# driver_V1_1.net
KiCad netlist of a schematic drawn in Altium Designer
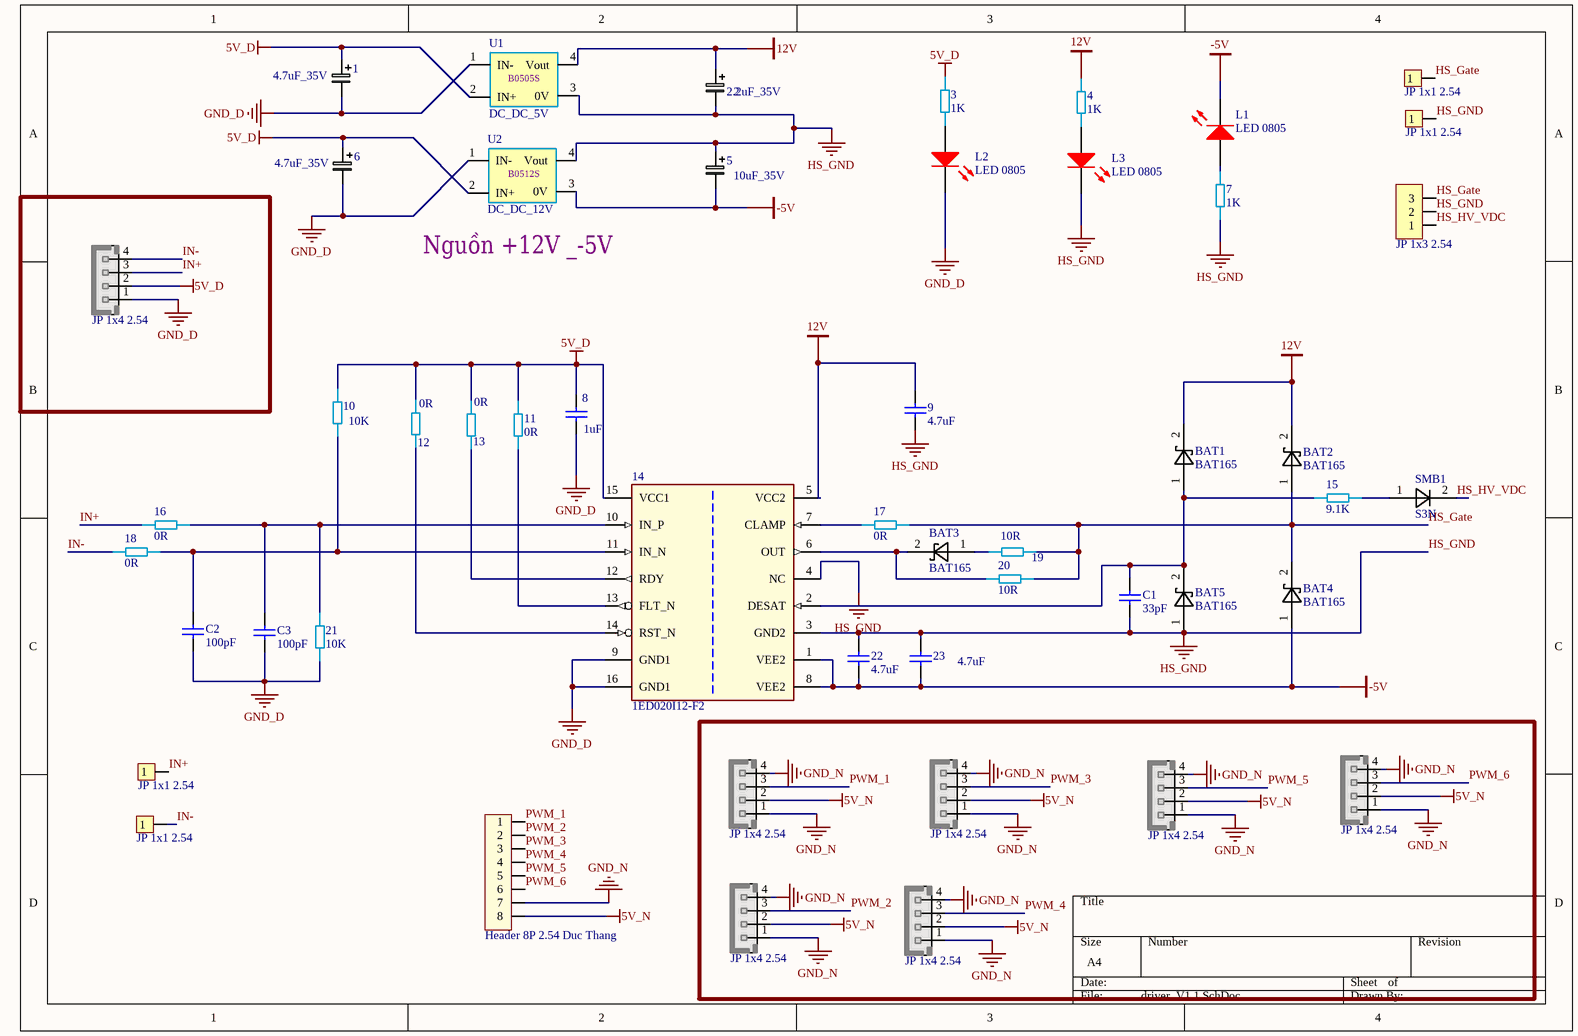
[diagram p0: driver_V1.1.SchDoc]

(export (version "E")
  (design (tool "Eeschema 10.0.6"))
  (components
    (comp (ref "1")
      (value "4.7uF_35V")
      (footprint "tu_4x5.4mm")
      (description "capacitor_electric")
      (libsource (lib "labari_altium1") (part "capacitor_electric"))
    )
    (comp (ref "2")
      (value "2.2uF_35V")
      (footprint "tu_4x5.4mm")
      (description "capacitor_electric")
      (libsource (lib "labari_altium1") (part "capacitor_electric"))
    )
    (comp (ref "3")
      (value "1K")
      (footprint "RES1206")
      (libsource (lib "labari_altium1") (part "311-0.0GRTR-ND"))
    )
    (comp (ref "4")
      (value "1K")
      (footprint "RES1206")
      (libsource (lib "labari_altium1") (part "311-0.0GRTR-ND"))
    )
    (comp (ref "5")
      (value "10uF_35V")
      (footprint "tu_4x5.4mm")
      (description "capacitor_electric")
      (libsource (lib "labari_altium1") (part "capacitor_electric"))
    )
    (comp (ref "6")
      (value "4.7uF_35V")
      (footprint "tu_4x5.4mm")
      (description "capacitor_electric")
      (libsource (lib "labari_altium1") (part "capacitor_electric"))
    )
    (comp (ref "7")
      (value "1K")
      (footprint "RES1206")
      (libsource (lib "labari_altium1") (part "311-0.0GRTR-ND"))
    )
    (comp (ref "8")
      (value "1uF")
      (footprint "Tu 0805_N")
      (libsource (lib "labari_altium1") (part "cap_0805"))
    )
    (comp (ref "9")
      (value "4.7uF")
      (footprint "tu 1206_N")
      (libsource (lib "labari_altium1") (part "cap_1210"))
    )
    (comp (ref "10")
      (value "10K")
      (footprint "RES1206")
      (libsource (lib "labari_altium1") (part "311-0.0GRTR-ND"))
    )
    (comp (ref "11")
      (value "0R")
      (footprint "RES1206")
      (libsource (lib "labari_altium1") (part "311-0.0GRTR-ND"))
    )
    (comp (ref "12")
      (value "0R")
      (footprint "RES1206")
      (libsource (lib "labari_altium1") (part "311-0.0GRTR-ND"))
    )
    (comp (ref "13")
      (value "0R")
      (footprint "RES1206")
      (libsource (lib "labari_altium1") (part "311-0.0GRTR-ND"))
    )
    (comp (ref "14")
      (value "1ED020I12-F2")
      (footprint "SOIC127P1028X264-16N-1")
      (description "Single IGBT Driver IC")
      (fields (field (name "MANUFACTURER") "Infineon Technologies"))
      (libsource (lib "labari_altium1") (part "1ED020I12-F2"))
    )
    (comp (ref "15")
      (value "9.1K")
      (footprint "RES_2512")
      (libsource (lib "labari_altium1") (part "311-0.0GRTR-ND"))
    )
    (comp (ref "16")
      (value "0R")
      (footprint "RES1206")
      (libsource (lib "labari_altium1") (part "311-0.0GRTR-ND"))
    )
    (comp (ref "17")
      (value "0R")
      (footprint "RES_2512")
      (libsource (lib "labari_altium1") (part "311-0.0GRTR-ND"))
    )
    (comp (ref "18")
      (value "0R")
      (footprint "RES1206")
      (libsource (lib "labari_altium1") (part "311-0.0GRTR-ND"))
    )
    (comp (ref "19")
      (value "10R")
      (footprint "RES_2512")
      (libsource (lib "labari_altium1") (part "311-0.0GRTR-ND"))
    )
    (comp (ref "20")
      (value "10R")
      (footprint "RES_2512")
      (libsource (lib "labari_altium1") (part "311-0.0GRTR-ND"))
    )
    (comp (ref "21")
      (value "10K")
      (footprint "RES1206")
      (libsource (lib "labari_altium1") (part "311-0.0GRTR-ND"))
    )
    (comp (ref "22")
      (value "4.7uF")
      (footprint "tu 1206_N")
      (libsource (lib "labari_altium1") (part "cap_1210"))
    )
    (comp (ref "23")
      (value "4.7uF")
      (footprint "tu 1206_N")
      (libsource (lib "labari_altium1") (part "cap_1210"))
    )
    (comp (ref "BAT1") (value "BAT165") (footprint "SMB") (libsource (lib "labari_altium1") (part "BAT165")))
    (comp (ref "BAT2") (value "BAT165") (footprint "SMB") (libsource (lib "labari_altium1") (part "BAT165")))
    (comp (ref "BAT3") (value "BAT165") (footprint "SMB") (libsource (lib "labari_altium1") (part "BAT165")))
    (comp (ref "BAT4") (value "BAT165") (footprint "SMB") (libsource (lib "labari_altium1") (part "BAT165")))
    (comp (ref "BAT5") (value "BAT165") (footprint "SMB") (libsource (lib "labari_altium1") (part "BAT165")))
    (comp (ref "C1")
      (value "33pF")
      (footprint "Tu 0805_N")
      (libsource (lib "labari_altium1") (part "cap_0805"))
    )
    (comp (ref "C2")
      (value "100pF")
      (footprint "Tu 0805_N")
      (libsource (lib "labari_altium1") (part "cap_0805"))
    )
    (comp (ref "C3")
      (value "100pF")
      (footprint "Tu 0805_N")
      (libsource (lib "labari_altium1") (part "cap_0805"))
    )
    (comp (ref "H1")
      (value "Header 8P 2.54 Duc Thang")
      (footprint "XH2.54M-8")
      (description "Cắm")
      (libsource (lib "labari_altium1") (part "Header 8P 2.54 Duc Thang"))
    )
    (comp (ref "JP1")
      (value "JP 1x1 2.54")
      (footprint "test_point")
      (description "Cắm")
      (libsource (lib "labari_altium1") (part "JP 1x1 2.54 Duc Thang"))
    )
    (comp (ref "JP2")
      (value "JP 1x1 2.54")
      (footprint "test_point")
      (description "Cắm")
      (libsource (lib "labari_altium1") (part "JP 1x1 2.54 Duc Thang"))
    )
    (comp (ref "JP3")
      (value "JP 1x3 2.54")
      (footprint "XH2.54M-3")
      (description "Cắm")
      (libsource (lib "labari_altium1") (part "JP 1x3 2.54 Duc Cong"))
    )
    (comp (ref "JP4")
      (value "JP 1x4 2.54")
      (footprint "XH2.54M-4")
      (description "Cắm")
      (libsource (lib "labari_altium1") (part "JP 1x4 2.54 Duc Thang"))
    )
    (comp (ref "JP5")
      (value "JP 1x1 2.54")
      (footprint "test_point")
      (description "Cắm")
      (libsource (lib "labari_altium1") (part "JP 1x1 2.54 Duc Thang"))
    )
    (comp (ref "JP6")
      (value "JP 1x1 2.54")
      (footprint "test_point")
      (description "Cắm")
      (libsource (lib "labari_altium1") (part "JP 1x1 2.54 Duc Thang"))
    )
    (comp (ref "JP7")
      (value "JP 1x4 2.54")
      (footprint "XH2.54M-4")
      (description "Cắm")
      (libsource (lib "labari_altium1") (part "JP 1x4 2.54 Duc Thang"))
    )
    (comp (ref "JP8")
      (value "JP 1x4 2.54")
      (footprint "XH2.54M-4")
      (description "Cắm")
      (libsource (lib "labari_altium1") (part "JP 1x4 2.54 Duc Thang"))
    )
    (comp (ref "JP9")
      (value "JP 1x4 2.54")
      (footprint "XH2.54M-4")
      (description "Cắm")
      (libsource (lib "labari_altium1") (part "JP 1x4 2.54 Duc Thang"))
    )
    (comp (ref "JP10")
      (value "JP 1x4 2.54")
      (footprint "XH2.54M-4")
      (description "Cắm")
      (libsource (lib "labari_altium1") (part "JP 1x4 2.54 Duc Thang"))
    )
    (comp (ref "JP11")
      (value "JP 1x4 2.54")
      (footprint "XH2.54M-4")
      (description "Cắm")
      (libsource (lib "labari_altium1") (part "JP 1x4 2.54 Duc Thang"))
    )
    (comp (ref "JP12")
      (value "JP 1x4 2.54")
      (footprint "XH2.54M-4")
      (description "Cắm")
      (libsource (lib "labari_altium1") (part "JP 1x4 2.54 Duc Thang"))
    )
    (comp (ref "L1")
      (value "LED 0805")
      (footprint "LED-0805-Red")
      (description "Dán")
      (libsource (lib "labari_altium1") (part "LED 0805 Do"))
    )
    (comp (ref "L2")
      (value "LED 0805")
      (footprint "LED-0805-Red")
      (description "Dán")
      (libsource (lib "labari_altium1") (part "LED 0805 Do"))
    )
    (comp (ref "L3")
      (value "LED 0805")
      (footprint "LED-0805-Red")
      (description "Dán")
      (libsource (lib "labari_altium1") (part "LED 0805 Do"))
    )
    (comp (ref "SMB1") (value "S3N") (footprint "SMB") (libsource (lib "labari_altium1") (part "S3A-S3N")))
    (comp (ref "U1")
      (value "DC_DC_5V")
      (footprint "B0505S/D-1W")
      (libsource (lib "labari_altium1") (part "DC_DC_5v"))
    )
    (comp (ref "U2")
      (value "DC_DC_12V")
      (footprint "B0512S/D-1W")
      (libsource (lib "labari_altium1") (part "DC_DC_12v"))
    )
  )
  (nets
    (net (code "1") (name "-5V") (class "Default")
      (node (ref "14") (pin "1") (pinfunction "VEE2_1") (pintype "power_in"))
      (node (ref "14") (pin "8") (pinfunction "VEE2_8") (pintype "power_in"))
      (node (ref "22") (pin "1") (pinfunction "1_1") (pintype "passive"))
      (node (ref "23") (pin "1") (pinfunction "1_1") (pintype "passive"))
      (node (ref "5") (pin "2") (pinfunction "2_2") (pintype "passive"))
      (node (ref "BAT4") (pin "1") (pinfunction "1_1") (pintype "passive"))
      (node (ref "L1") (pin "2") (pinfunction "K_2") (pintype "passive"))
      (node (ref "U2") (pin "3") (pinfunction "0V_3") (pintype "passive"))
    )
    (net (code "2") (name "/HS_Gate") (class "Default")
      (node (ref "17") (pin "2") (pinfunction "2_2") (pintype "passive"))
      (node (ref "19") (pin "2") (pinfunction "2_2") (pintype "passive"))
      (node (ref "20") (pin "2") (pinfunction "2_2") (pintype "passive"))
      (node (ref "BAT2") (pin "1") (pinfunction "1_1") (pintype "passive"))
      (node (ref "BAT4") (pin "2") (pinfunction "2_2") (pintype "passive"))
      (node (ref "JP1") (pin "1") (pinfunction "1_1") (pintype "passive"))
      (node (ref "JP3") (pin "3") (pinfunction "3_3") (pintype "passive"))
    )
    (net (code "3") (name "/HS_HV_VDC") (class "Default")
      (node (ref "JP3") (pin "1") (pinfunction "1_1") (pintype "passive"))
      (node (ref "SMB1") (pin "2") (pinfunction "2_2") (pintype "passive"))
    )
    (net (code "4") (name "/IN+") (class "Default")
      (node (ref "16") (pin "2") (pinfunction "2_2") (pintype "passive"))
      (node (ref "JP4") (pin "3") (pinfunction "3_3") (pintype "passive"))
      (node (ref "JP5") (pin "1") (pinfunction "1_1") (pintype "passive"))
    )
    (net (code "5") (name "/IN-") (class "Default")
      (node (ref "18") (pin "2") (pinfunction "2_2") (pintype "passive"))
      (node (ref "JP4") (pin "4") (pinfunction "4_4") (pintype "passive"))
      (node (ref "JP6") (pin "1") (pinfunction "1_1") (pintype "passive"))
    )
    (net (code "6") (name "/PWM_1") (class "Default")
      (node (ref "H1") (pin "1") (pinfunction "1_1") (pintype "passive"))
      (node (ref "JP8") (pin "3") (pinfunction "3_3") (pintype "passive"))
    )
    (net (code "7") (name "/PWM_2") (class "Default")
      (node (ref "H1") (pin "2") (pinfunction "2_2") (pintype "passive"))
      (node (ref "JP11") (pin "3") (pinfunction "3_3") (pintype "passive"))
    )
    (net (code "8") (name "/PWM_3") (class "Default")
      (node (ref "H1") (pin "3") (pinfunction "3_3") (pintype "passive"))
      (node (ref "JP9") (pin "3") (pinfunction "3_3") (pintype "passive"))
    )
    (net (code "9") (name "/PWM_4") (class "Default")
      (node (ref "H1") (pin "4") (pinfunction "4_4") (pintype "passive"))
      (node (ref "JP12") (pin "3") (pinfunction "3_3") (pintype "passive"))
    )
    (net (code "10") (name "/PWM_5") (class "Default")
      (node (ref "H1") (pin "5") (pinfunction "5_5") (pintype "passive"))
      (node (ref "JP10") (pin "3") (pinfunction "3_3") (pintype "passive"))
    )
    (net (code "11") (name "/PWM_6") (class "Default")
      (node (ref "H1") (pin "6") (pinfunction "6_6") (pintype "passive"))
      (node (ref "JP7") (pin "3") (pinfunction "3_3") (pintype "passive"))
    )
    (net (code "12") (name "5V_D") (class "Default")
      (node (ref "1") (pin "1") (pinfunction "1_1") (pintype "passive"))
      (node (ref "10") (pin "2") (pinfunction "2_2") (pintype "passive"))
      (node (ref "11") (pin "1") (pinfunction "1_1") (pintype "passive"))
      (node (ref "12") (pin "2") (pinfunction "2_2") (pintype "passive"))
      (node (ref "13") (pin "1") (pinfunction "1_1") (pintype "passive"))
      (node (ref "14") (pin "15") (pinfunction "VCC1_15") (pintype "power_in"))
      (node (ref "3") (pin "1") (pinfunction "1_1") (pintype "passive"))
      (node (ref "6") (pin "1") (pinfunction "1_1") (pintype "passive"))
      (node (ref "8") (pin "2") (pinfunction "2_2") (pintype "passive"))
      (node (ref "JP4") (pin "2") (pinfunction "2_2") (pintype "passive"))
      (node (ref "U1") (pin "2") (pinfunction "IN+_2") (pintype "passive"))
      (node (ref "U2") (pin "2") (pinfunction "IN+_2") (pintype "passive"))
    )
    (net (code "13") (name "5V_N") (class "Default")
      (node (ref "H1") (pin "8") (pinfunction "8_8") (pintype "passive"))
      (node (ref "JP10") (pin "2") (pinfunction "2_2") (pintype "passive"))
      (node (ref "JP11") (pin "2") (pinfunction "2_2") (pintype "passive"))
      (node (ref "JP12") (pin "2") (pinfunction "2_2") (pintype "passive"))
      (node (ref "JP7") (pin "2") (pinfunction "2_2") (pintype "passive"))
      (node (ref "JP8") (pin "2") (pinfunction "2_2") (pintype "passive"))
      (node (ref "JP9") (pin "2") (pinfunction "2_2") (pintype "passive"))
    )
    (net (code "14") (name "12V") (class "Default")
      (node (ref "14") (pin "5") (pinfunction "VCC2_5") (pintype "power_in"))
      (node (ref "2") (pin "1") (pinfunction "1_1") (pintype "passive"))
      (node (ref "4") (pin "1") (pinfunction "1_1") (pintype "passive"))
      (node (ref "9") (pin "2") (pinfunction "2_2") (pintype "passive"))
      (node (ref "BAT1") (pin "2") (pinfunction "2_2") (pintype "passive"))
      (node (ref "BAT2") (pin "2") (pinfunction "2_2") (pintype "passive"))
      (node (ref "U1") (pin "4") (pinfunction "Vout_4") (pintype "passive"))
    )
    (net (code "15") (name "GND_D") (class "Default")
      (node (ref "1") (pin "2") (pinfunction "2_2") (pintype "passive"))
      (node (ref "14") (pin "16") (pinfunction "GND1_16") (pintype "power_in"))
      (node (ref "14") (pin "9") (pinfunction "GND1_9") (pintype "power_in"))
      (node (ref "21") (pin "2") (pinfunction "2_2") (pintype "passive"))
      (node (ref "6") (pin "2") (pinfunction "2_2") (pintype "passive"))
      (node (ref "8") (pin "1") (pinfunction "1_1") (pintype "passive"))
      (node (ref "C2") (pin "1") (pinfunction "1_1") (pintype "passive"))
      (node (ref "C3") (pin "1") (pinfunction "1_1") (pintype "passive"))
      (node (ref "JP4") (pin "1") (pinfunction "1_1") (pintype "passive"))
      (node (ref "L2") (pin "2") (pinfunction "K_2") (pintype "passive"))
      (node (ref "U1") (pin "1") (pinfunction "IN-_1") (pintype "passive"))
      (node (ref "U2") (pin "1") (pinfunction "IN-_1") (pintype "passive"))
    )
    (net (code "16") (name "GND_N") (class "Default")
      (node (ref "H1") (pin "7") (pinfunction "7_7") (pintype "passive"))
      (node (ref "JP10") (pin "1") (pinfunction "1_1") (pintype "passive"))
      (node (ref "JP10") (pin "4") (pinfunction "4_4") (pintype "passive"))
      (node (ref "JP11") (pin "1") (pinfunction "1_1") (pintype "passive"))
      (node (ref "JP11") (pin "4") (pinfunction "4_4") (pintype "passive"))
      (node (ref "JP12") (pin "1") (pinfunction "1_1") (pintype "passive"))
      (node (ref "JP12") (pin "4") (pinfunction "4_4") (pintype "passive"))
      (node (ref "JP7") (pin "1") (pinfunction "1_1") (pintype "passive"))
      (node (ref "JP7") (pin "4") (pinfunction "4_4") (pintype "passive"))
      (node (ref "JP8") (pin "1") (pinfunction "1_1") (pintype "passive"))
      (node (ref "JP8") (pin "4") (pinfunction "4_4") (pintype "passive"))
      (node (ref "JP9") (pin "1") (pinfunction "1_1") (pintype "passive"))
      (node (ref "JP9") (pin "4") (pinfunction "4_4") (pintype "passive"))
    )
    (net (code "17") (name "HS_GND") (class "Default")
      (node (ref "14") (pin "3") (pinfunction "GND2_3") (pintype "power_in"))
      (node (ref "14") (pin "4") (pinfunction "NC_4") (pintype "passive"))
      (node (ref "2") (pin "2") (pinfunction "2_2") (pintype "passive"))
      (node (ref "22") (pin "2") (pinfunction "2_2") (pintype "passive"))
      (node (ref "23") (pin "2") (pinfunction "2_2") (pintype "passive"))
      (node (ref "5") (pin "1") (pinfunction "1_1") (pintype "passive"))
      (node (ref "7") (pin "2") (pinfunction "2_2") (pintype "passive"))
      (node (ref "9") (pin "1") (pinfunction "1_1") (pintype "passive"))
      (node (ref "BAT5") (pin "1") (pinfunction "1_1") (pintype "passive"))
      (node (ref "C1") (pin "1") (pinfunction "1_1") (pintype "passive"))
      (node (ref "JP2") (pin "1") (pinfunction "1_1") (pintype "passive"))
      (node (ref "JP3") (pin "2") (pinfunction "2_2") (pintype "passive"))
      (node (ref "L3") (pin "2") (pinfunction "K_2") (pintype "passive"))
      (node (ref "U1") (pin "3") (pinfunction "0V_3") (pintype "passive"))
      (node (ref "U2") (pin "4") (pinfunction "Vout_4") (pintype "passive"))
    )
    (net (code "18") (name "Net-(14-CLAMP)") (class "Default")
      (node (ref "14") (pin "7") (pinfunction "CLAMP_7") (pintype "input"))
      (node (ref "17") (pin "1") (pinfunction "1_1") (pintype "passive"))
    )
    (net (code "19") (name "Net-(14-DESAT)") (class "Default")
      (node (ref "14") (pin "2") (pinfunction "DESAT_2") (pintype "input"))
      (node (ref "15") (pin "1") (pinfunction "1_1") (pintype "passive"))
      (node (ref "BAT1") (pin "1") (pinfunction "1_1") (pintype "passive"))
      (node (ref "BAT5") (pin "2") (pinfunction "2_2") (pintype "passive"))
      (node (ref "C1") (pin "2") (pinfunction "2_2") (pintype "passive"))
    )
    (net (code "20") (name "Net-(14-FLT_N)") (class "Default")
      (node (ref "11") (pin "2") (pinfunction "2_2") (pintype "passive"))
      (node (ref "14") (pin "13") (pinfunction "FLT_N_13") (pintype "output"))
    )
    (net (code "21") (name "Net-(14-IN_N)") (class "Default")
      (node (ref "10") (pin "1") (pinfunction "1_1") (pintype "passive"))
      (node (ref "14") (pin "11") (pinfunction "IN_N_11") (pintype "input"))
      (node (ref "18") (pin "1") (pinfunction "1_1") (pintype "passive"))
      (node (ref "C2") (pin "2") (pinfunction "2_2") (pintype "passive"))
    )
    (net (code "22") (name "Net-(14-IN_P)") (class "Default")
      (node (ref "14") (pin "10") (pinfunction "IN_P_10") (pintype "input"))
      (node (ref "16") (pin "1") (pinfunction "1_1") (pintype "passive"))
      (node (ref "21") (pin "1") (pinfunction "1_1") (pintype "passive"))
      (node (ref "C3") (pin "2") (pinfunction "2_2") (pintype "passive"))
    )
    (net (code "23") (name "Net-(14-OUT)") (class "Default")
      (node (ref "14") (pin "6") (pinfunction "OUT_6") (pintype "output"))
      (node (ref "20") (pin "1") (pinfunction "1_1") (pintype "passive"))
      (node (ref "BAT3") (pin "2") (pinfunction "2_2") (pintype "passive"))
    )
    (net (code "24") (name "Net-(14-RDY)") (class "Default")
      (node (ref "13") (pin "2") (pinfunction "2_2") (pintype "passive"))
      (node (ref "14") (pin "12") (pinfunction "RDY_12") (pintype "output"))
    )
    (net (code "25") (name "Net-(14-RST_N)") (class "Default")
      (node (ref "12") (pin "1") (pinfunction "1_1") (pintype "passive"))
      (node (ref "14") (pin "14") (pinfunction "RST_N_14") (pintype "input"))
    )
    (net (code "26") (name "Net-(15-Pad2)") (class "Default")
      (node (ref "15") (pin "2") (pinfunction "2_2") (pintype "passive"))
      (node (ref "SMB1") (pin "1") (pinfunction "1_1") (pintype "passive"))
    )
    (net (code "27") (name "Net-(19-Pad1)") (class "Default")
      (node (ref "19") (pin "1") (pinfunction "1_1") (pintype "passive"))
      (node (ref "BAT3") (pin "1") (pinfunction "1_1") (pintype "passive"))
    )
    (net (code "28") (name "Net-(L1-A)") (class "Default")
      (node (ref "7") (pin "1") (pinfunction "1_1") (pintype "passive"))
      (node (ref "L1") (pin "1") (pinfunction "A_1") (pintype "passive"))
    )
    (net (code "29") (name "Net-(L2-A)") (class "Default")
      (node (ref "3") (pin "2") (pinfunction "2_2") (pintype "passive"))
      (node (ref "L2") (pin "1") (pinfunction "A_1") (pintype "passive"))
    )
    (net (code "30") (name "Net-(L3-A)") (class "Default")
      (node (ref "4") (pin "2") (pinfunction "2_2") (pintype "passive"))
      (node (ref "L3") (pin "1") (pinfunction "A_1") (pintype "passive"))
    )
  )
)
